# Transmitter_Schematic.net
KiCad netlist of a schematic drawn in Altium Designer
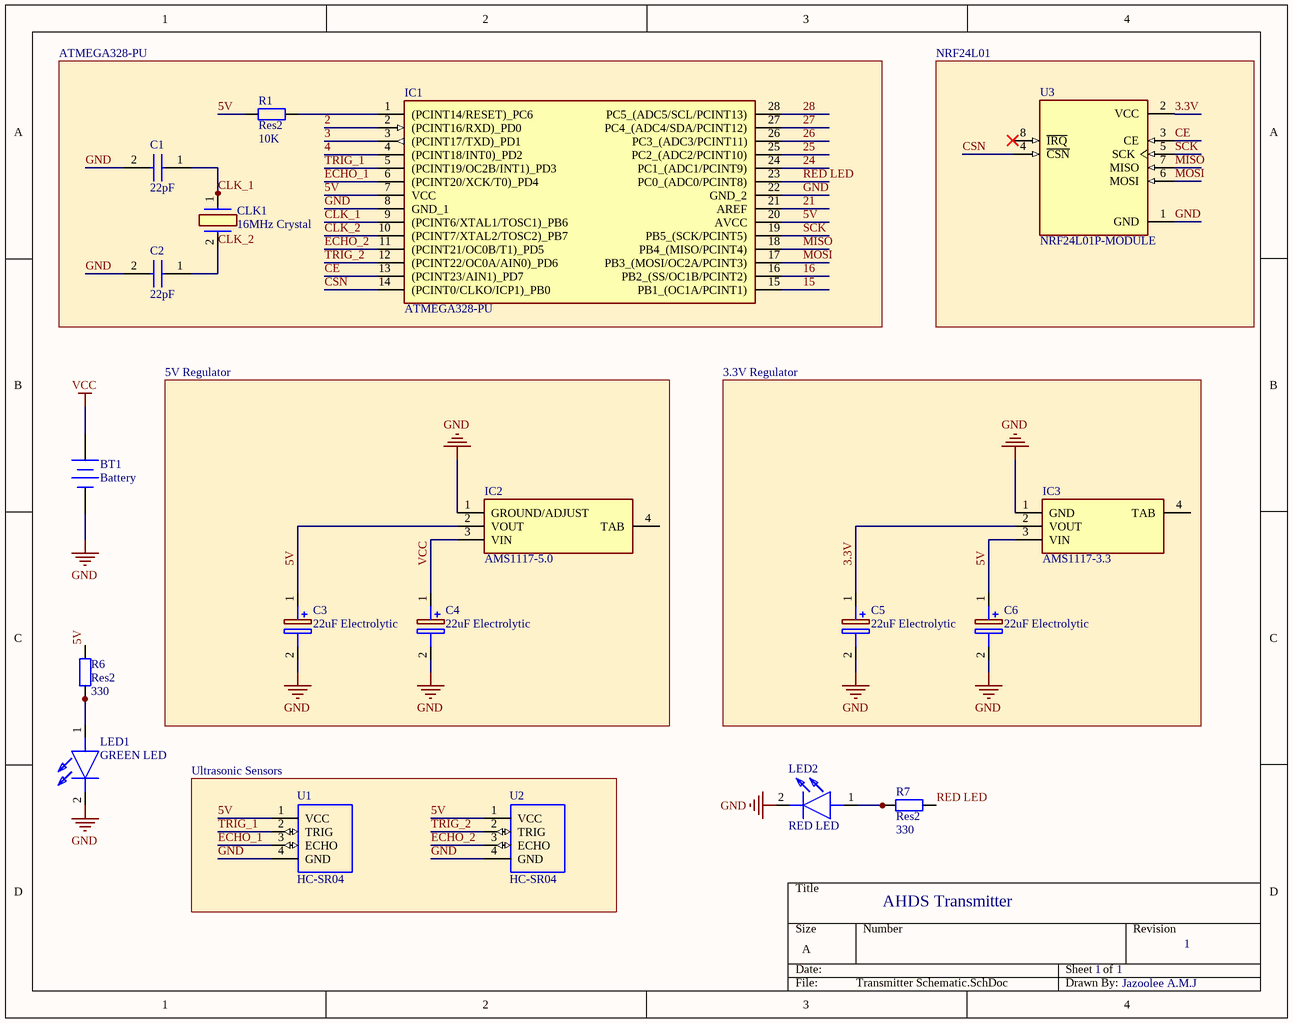
[diagram p0: Transmitter Schematic.SchDoc]

(export (version "E")
  (design (tool "Eeschema 10.0.6"))
  (components
    (comp (ref "BT1")
      (value "Battery")
      (footprint "BAT-2")
      (description "Multicell Battery")
      (fields (field (name "PUBLISHER") "Altium Limited"))
      (libsource (lib "Miscellaneous Devices") (part "Battery"))
    )
    (comp (ref "C1")
      (value "22pF")
      (footprint "SamacSys:S220K25SL0N63L6R")
      (description "Capacitor Ceramic THT")
      (fields
        (field (name "MANUFACTURER_PART_NUMBER") "S220K25SL0N63L6R")
        (field (name "MOUSER PART NUMBER") "594-S220K25SL0N63L6R")
      )
      (libsource (lib "*") (part "S220K25SL0N63L6R"))
    )
    (comp (ref "C2")
      (value "22pF")
      (footprint "SamacSys:S220K25SL0N63L6R")
      (description "Capacitor Ceramic THT")
      (fields
        (field (name "MANUFACTURER_PART_NUMBER") "S220K25SL0N63L6R")
        (field (name "MOUSER PART NUMBER") "594-S220K25SL0N63L6R")
      )
      (libsource (lib "*") (part "S220K25SL0N63L6R"))
    )
    (comp (ref "C3")
      (value "22uF Electrolytic")
      (footprint "SamacSys:CAPPRD250W55D630H1220")
      (description "Capacitor Polarised")
      (fields (field (name "MANUFACTURER_PART_NUMBER") "ECA1EEN220"))
      (libsource (lib "*") (part "ECA1EEN220"))
    )
    (comp (ref "C4")
      (value "22uF Electrolytic")
      (footprint "SamacSys:CAPPRD250W55D630H1220")
      (description "Capacitor Polarised")
      (fields (field (name "MANUFACTURER_PART_NUMBER") "ECA1EEN220"))
      (libsource (lib "*") (part "ECA1EEN220"))
    )
    (comp (ref "C5")
      (value "22uF Electrolytic")
      (footprint "SamacSys:CAPPRD250W55D630H1220")
      (description "Capacitor Polarised")
      (fields (field (name "MANUFACTURER_PART_NUMBER") "ECA1EEN220"))
      (libsource (lib "*") (part "ECA1EEN220"))
    )
    (comp (ref "C6")
      (value "22uF Electrolytic")
      (footprint "SamacSys:CAPPRD250W55D630H1220")
      (description "Capacitor Polarised")
      (fields (field (name "MANUFACTURER_PART_NUMBER") "ECA1EEN220"))
      (libsource (lib "*") (part "ECA1EEN220"))
    )
    (comp (ref "CLK1")
      (value "16MHz Crystal")
      (footprint "SamacSys:LFXTAL036391Bulk")
      (description "Crystal or Oscillator")
      (fields
        (field (name "MANUFACTURER_PART_NUMBER") "LFXTAL036391Bulk")
        (field (name "MOUSER PART NUMBER") "449-LFXTAL036391BULK")
      )
      (libsource (lib "*") (part "LFXTAL036391Bulk"))
    )
    (comp (ref "IC1")
      (value "ATMEGA328-PU")
      (footprint "SamacSys:DIP1016W53P254L3468H457Q28N")
      (description "Integrated Circuit")
      (fields (field (name "MOUSER PART NUMBER") "556-ATMEGA328-PU"))
      (libsource (lib "*") (part "ATMEGA328-PU"))
    )
    (comp (ref "IC2")
      (value "AMS1117-5.0")
      (footprint "SamacSys:SOT229P700X180-4N")
      (description "Integrated Circuit")
      (libsource (lib "*") (part "AMS1117-5.0"))
    )
    (comp (ref "IC3")
      (value "AMS1117-3.3")
      (footprint "SamacSys:SOT229P700X180-4N")
      (description "Integrated Circuit")
      (libsource (lib "*") (part "AMS1117-3.3"))
    )
    (comp (ref "LED1")
      (value "GREEN LED")
      (footprint "SamacSys:125410SURTS530A3")
      (description "LED")
      (fields (field (name "MANUFACTURER_PART_NUMBER") "1254-10SURT/S530-A3"))
      (libsource (lib "*") (part "1254-10SURT_S530-A3"))
    )
    (comp (ref "LED2")
      (value "RED LED")
      (footprint "SamacSys:125410SURTS530A3")
      (description "LED")
      (fields (field (name "MANUFACTURER_PART_NUMBER") "1254-10SURT/S530-A3"))
      (libsource (lib "*") (part "1254-10SURT_S530-A3"))
    )
    (comp (ref "R1")
      (value "Res2")
      (footprint "AXIAL-0.4")
      (description "Resistor")
      (fields (field (name "ALTIUM_VALUE") "10K") (field (name "PUBLISHER") "Altium Limited"))
      (libsource (lib "") (part "Res2_1"))
    )
    (comp (ref "R6")
      (value "Res2")
      (footprint "AXIAL-0.4")
      (description "Resistor")
      (fields (field (name "ALTIUM_VALUE") "330") (field (name "PUBLISHER") "Altium Limited"))
      (libsource (lib "Miscellaneous Devices") (part "Res2"))
    )
    (comp (ref "R7")
      (value "Res2")
      (footprint "AXIAL-0.4")
      (description "Resistor")
      (fields (field (name "ALTIUM_VALUE") "330") (field (name "PUBLISHER") "Altium Limited"))
      (libsource (lib "") (part "Res2_1"))
    )
    (comp (ref "U1")
      (value "HC-SR04")
      (footprint "XCVR_HC-SR04")
      (description "Ultrasonic Sensor Module")
      (libsource (lib "HC-SR04") (part "HC-SR04"))
    )
    (comp (ref "U2")
      (value "HC-SR04")
      (footprint "XCVR_HC-SR04")
      (description "Ultrasonic Sensor Module")
      (libsource (lib "HC-SR04") (part "HC-SR04"))
    )
    (comp (ref "U3")
      (value "NRF24L01P-MODULE")
      (footprint "XCVR_NRF24L01P-MODULE-PCB")
      (description "- Transceiver For Use With nRF24L01+")
      (fields (field (name "MP") "NRF24L01P-MODULE-PCB") (field (name "MF") "Nordic Semiconductor"))
      (libsource (lib "NRF24L01P-MODULE-PCB") (part "NRF24L01P-MODULE-PCB"))
    )
  )
  (nets
    (net (code "1") (name "/2") (class "Default")
      (node (ref "IC1") (pin "2") (pinfunction "(PCINT16/RXD)_PD0_2") (pintype "input"))
    )
    (net (code "2") (name "/3") (class "Default")
      (node (ref "IC1") (pin "3") (pinfunction "(PCINT17/TXD)_PD1_3") (pintype "output"))
    )
    (net (code "3") (name "/3.3V") (class "Default")
      (node (ref "C5") (pin "1") (pinfunction "+_1") (pintype "passive"))
      (node (ref "IC3") (pin "2") (pinfunction "VOUT_2") (pintype "passive"))
      (node (ref "U3") (pin "2") (pinfunction "VCC_2") (pintype "power_in"))
    )
    (net (code "4") (name "/4") (class "Default")
      (node (ref "IC1") (pin "4") (pinfunction "(PCINT18/INT0)_PD2_4") (pintype "passive"))
    )
    (net (code "5") (name "/5V") (class "Default")
      (node (ref "C3") (pin "1") (pinfunction "+_1") (pintype "passive"))
      (node (ref "C6") (pin "1") (pinfunction "+_1") (pintype "passive"))
      (node (ref "IC1") (pin "20") (pinfunction "AVCC_20") (pintype "power_in"))
      (node (ref "IC1") (pin "7") (pinfunction "VCC_7") (pintype "power_in"))
      (node (ref "IC2") (pin "2") (pinfunction "VOUT_2") (pintype "passive"))
      (node (ref "IC3") (pin "3") (pinfunction "VIN_3") (pintype "passive"))
      (node (ref "R1") (pin "1") (pinfunction "1_1") (pintype "passive"))
      (node (ref "R6") (pin "2") (pinfunction "2_2") (pintype "passive"))
      (node (ref "U1") (pin "1") (pinfunction "VCC_1") (pintype "power_in"))
      (node (ref "U2") (pin "1") (pinfunction "VCC_1") (pintype "power_in"))
    )
    (net (code "6") (name "/15") (class "Default")
      (node (ref "IC1") (pin "15") (pinfunction "PB1_(OC1A/PCINT1)_15") (pintype "passive"))
    )
    (net (code "7") (name "/16") (class "Default")
      (node (ref "IC1") (pin "16") (pinfunction "PB2_(SS/OC1B/PCINT2)_16") (pintype "passive"))
    )
    (net (code "8") (name "/21") (class "Default")
      (node (ref "IC1") (pin "21") (pinfunction "AREF_21") (pintype "passive"))
    )
    (net (code "9") (name "/24") (class "Default")
      (node (ref "IC1") (pin "24") (pinfunction "PC1_(ADC1/PCINT9)_24") (pintype "passive"))
    )
    (net (code "10") (name "/25") (class "Default")
      (node (ref "IC1") (pin "25") (pinfunction "PC2_(ADC2/PCINT10)_25") (pintype "passive"))
    )
    (net (code "11") (name "/26") (class "Default")
      (node (ref "IC1") (pin "26") (pinfunction "PC3_(ADC3/PCINT11)_26") (pintype "passive"))
    )
    (net (code "12") (name "/27") (class "Default")
      (node (ref "IC1") (pin "27") (pinfunction "PC4_(ADC4/SDA/PCINT12)_27") (pintype "passive"))
    )
    (net (code "13") (name "/28") (class "Default")
      (node (ref "IC1") (pin "28") (pinfunction "PC5_(ADC5/SCL/PCINT13)_28") (pintype "passive"))
    )
    (net (code "14") (name "/CE") (class "Default")
      (node (ref "IC1") (pin "13") (pinfunction "(PCINT23/AIN1)_PD7_13") (pintype "passive"))
      (node (ref "U3") (pin "3") (pinfunction "CE_3") (pintype "input"))
    )
    (net (code "15") (name "/CLK_1") (class "Default")
      (node (ref "C1") (pin "1") (pinfunction "1_1") (pintype "passive"))
      (node (ref "CLK1") (pin "1") (pinfunction "CRYSTAL_1_1") (pintype "passive"))
      (node (ref "IC1") (pin "9") (pinfunction "(PCINT6/XTAL1/TOSC1)_PB6_9") (pintype "passive"))
    )
    (net (code "16") (name "/CLK_2") (class "Default")
      (node (ref "C2") (pin "1") (pinfunction "1_1") (pintype "passive"))
      (node (ref "CLK1") (pin "2") (pinfunction "CRYSTAL_2_2") (pintype "passive"))
      (node (ref "IC1") (pin "10") (pinfunction "(PCINT7/XTAL2/TOSC2)_PB7_10") (pintype "passive"))
    )
    (net (code "17") (name "/CSN") (class "Default")
      (node (ref "IC1") (pin "14") (pinfunction "(PCINT0/CLKO/ICP1)_PB0_14") (pintype "passive"))
      (node (ref "U3") (pin "4") (pinfunction "~{CSN}_4") (pintype "input"))
    )
    (net (code "18") (name "/ECHO_1") (class "Default")
      (node (ref "IC1") (pin "6") (pinfunction "(PCINT20/XCK/T0)_PD4_6") (pintype "passive"))
      (node (ref "U1") (pin "3") (pinfunction "ECHO_3") (pintype "bidirectional"))
    )
    (net (code "19") (name "/ECHO_2") (class "Default")
      (node (ref "IC1") (pin "11") (pinfunction "(PCINT21/OC0B/T1)_PD5_11") (pintype "passive"))
      (node (ref "U2") (pin "3") (pinfunction "ECHO_3") (pintype "bidirectional"))
    )
    (net (code "20") (name "/MISO") (class "Default")
      (node (ref "IC1") (pin "18") (pinfunction "PB4_(MISO/PCINT4)_18") (pintype "passive"))
      (node (ref "U3") (pin "7") (pinfunction "MISO_7") (pintype "input"))
    )
    (net (code "21") (name "/MOSI") (class "Default")
      (node (ref "IC1") (pin "17") (pinfunction "PB3_(MOSI/OC2A/PCINT3)_17") (pintype "passive"))
      (node (ref "U3") (pin "6") (pinfunction "MOSI_6") (pintype "input"))
    )
    (net (code "22") (name "/RED LED") (class "Default")
      (node (ref "IC1") (pin "23") (pinfunction "PC0_(ADC0/PCINT8)_23") (pintype "passive"))
      (node (ref "R7") (pin "2") (pinfunction "2_2") (pintype "passive"))
    )
    (net (code "23") (name "/SCK") (class "Default")
      (node (ref "IC1") (pin "19") (pinfunction "PB5_(SCK/PCINT5)_19") (pintype "passive"))
      (node (ref "U3") (pin "5") (pinfunction "SCK_5") (pintype "input"))
    )
    (net (code "24") (name "/TRIG_1") (class "Default")
      (node (ref "IC1") (pin "5") (pinfunction "(PCINT19/OC2B/INT1)_PD3_5") (pintype "passive"))
      (node (ref "U1") (pin "2") (pinfunction "TRIG_2") (pintype "bidirectional"))
    )
    (net (code "25") (name "/TRIG_2") (class "Default")
      (node (ref "IC1") (pin "12") (pinfunction "(PCINT22/OC0A/AIN0)_PD6_12") (pintype "passive"))
      (node (ref "U2") (pin "2") (pinfunction "TRIG_2") (pintype "bidirectional"))
    )
    (net (code "26") (name "GND") (class "Default")
      (node (ref "BT1") (pin "2") (pinfunction "-_2") (pintype "passive"))
      (node (ref "C1") (pin "2") (pinfunction "2_2") (pintype "passive"))
      (node (ref "C2") (pin "2") (pinfunction "2_2") (pintype "passive"))
      (node (ref "C3") (pin "2") (pinfunction "-_2") (pintype "passive"))
      (node (ref "C4") (pin "2") (pinfunction "-_2") (pintype "passive"))
      (node (ref "C5") (pin "2") (pinfunction "-_2") (pintype "passive"))
      (node (ref "C6") (pin "2") (pinfunction "-_2") (pintype "passive"))
      (node (ref "IC1") (pin "22") (pinfunction "GND_2_22") (pintype "power_in"))
      (node (ref "IC1") (pin "8") (pinfunction "GND_1_8") (pintype "power_in"))
      (node (ref "IC2") (pin "1") (pinfunction "GROUND/ADJUST_1") (pintype "passive"))
      (node (ref "IC3") (pin "1") (pinfunction "GND_1") (pintype "passive"))
      (node (ref "LED1") (pin "2") (pinfunction "K_2") (pintype "passive"))
      (node (ref "LED2") (pin "2") (pinfunction "K_2") (pintype "passive"))
      (node (ref "U1") (pin "4") (pinfunction "GND_4") (pintype "power_in"))
      (node (ref "U2") (pin "4") (pinfunction "GND_4") (pintype "power_in"))
      (node (ref "U3") (pin "1") (pinfunction "GND_1") (pintype "power_in"))
    )
    (net (code "27") (name "Net-(IC1-(PCINT14{slash}RESET)_PC6)") (class "Default")
      (node (ref "IC1") (pin "1") (pinfunction "(PCINT14/RESET)_PC6_1") (pintype "passive"))
      (node (ref "R1") (pin "2") (pinfunction "2_2") (pintype "passive"))
    )
    (net (code "28") (name "Net-(LED1-A)") (class "Default")
      (node (ref "LED1") (pin "1") (pinfunction "A_1") (pintype "passive"))
      (node (ref "R6") (pin "1") (pinfunction "1_1") (pintype "passive"))
    )
    (net (code "29") (name "Net-(LED2-A)") (class "Default")
      (node (ref "LED2") (pin "1") (pinfunction "A_1") (pintype "passive"))
      (node (ref "R7") (pin "1") (pinfunction "1_1") (pintype "passive"))
    )
    (net (code "30") (name "VCC") (class "Default")
      (node (ref "BT1") (pin "1") (pinfunction "+_1") (pintype "passive"))
      (node (ref "C4") (pin "1") (pinfunction "+_1") (pintype "passive"))
      (node (ref "IC2") (pin "3") (pinfunction "VIN_3") (pintype "passive"))
    )
    (net (code "31") (name "unconnected-(IC2-TAB-Pad4)") (class "Default")
      (node (ref "IC2") (pin "4") (pinfunction "TAB_4") (pintype "passive"))
    )
    (net (code "32") (name "unconnected-(IC3-TAB-Pad4)") (class "Default")
      (node (ref "IC3") (pin "4") (pinfunction "TAB_4") (pintype "passive"))
    )
    (net (code "33") (name "unconnected-(U3-~{IRQ}-Pad8)") (class "Default")
      (node (ref "U3") (pin "8") (pinfunction "~{IRQ}_8") (pintype "input+no_connect"))
    )
  )
)
